# 07_Buzzer.net
KiCad netlist of a schematic drawn in Altium Designer
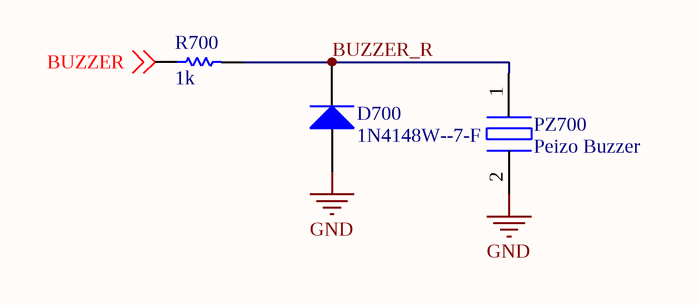
[diagram p0: 07_Buzzer.SchDoc]

(export (version "E")
  (design (tool "Eeschema 10.0.6"))
  (components
    (comp (ref "D700")
      (value "DIODE_4148")
      (footprint "SOD323-12")
      (description "DIODE GEN PURP 100V 300MA SOD123")
      (fields (field (name "MANUFACTURER") "Diodes") (field (name "MANUFACTURER PART NUMBER") "1N4148W--7-F"))
      (libsource (lib "ece315-2017-fall") (part "DIODE_4148"))
    )
    (comp (ref "PZ700")
      (value "Peizo Buzzer")
      (footprint "PKLCS")
      (description "AUDIO PIEZO TRANSDUCER 12.5V SMD")
      (fields
        (field (name "MANUFACTURER PART NUMBER") "PKLCS1212E2000-R1")
        (field (name "MANUFACTURER") "Murata Electronics North America")
      )
      (libsource (lib "ece315-2017-fall") (part "Peizo"))
    )
    (comp (ref "R700")
      (value "RES_0805_K_001.00")
      (footprint "RES_0805")
      (description "RES SMD 1K OHM 1% 1/8W 0805")
      (fields
        (field (name "MANUFACTURER PART NUMBER") "ERJ-6ENF1001V")
        (field (name "TOLERANCE") "±1%")
        (field (name "RESISTANCE (OHMS)") "1k")
      )
      (libsource (lib "ece315-2017-fall") (part "RES_0805_K_001.00"))
    )
  )
  (nets
    (net (code "1") (name "/BUZZER_R") (class "Default")
      (node (ref "D700") (pin "1") (pinfunction "K_1") (pintype "passive"))
      (node (ref "PZ700") (pin "1") (pinfunction "In_1") (pintype "passive"))
      (node (ref "R700") (pin "2") (pinfunction "2_2") (pintype "passive"))
    )
    (net (code "2") (name "BUZZER") (class "Default")
      (node (ref "R700") (pin "1") (pinfunction "1_1") (pintype "passive"))
    )
    (net (code "3") (name "GND") (class "Default")
      (node (ref "D700") (pin "2") (pinfunction "A_2") (pintype "passive"))
      (node (ref "PZ700") (pin "2") (pinfunction "In_2") (pintype "passive"))
    )
  )
)
